# LucidVRSensorPCB_Side.net
KiCad netlist of a schematic drawn in EasyEDA
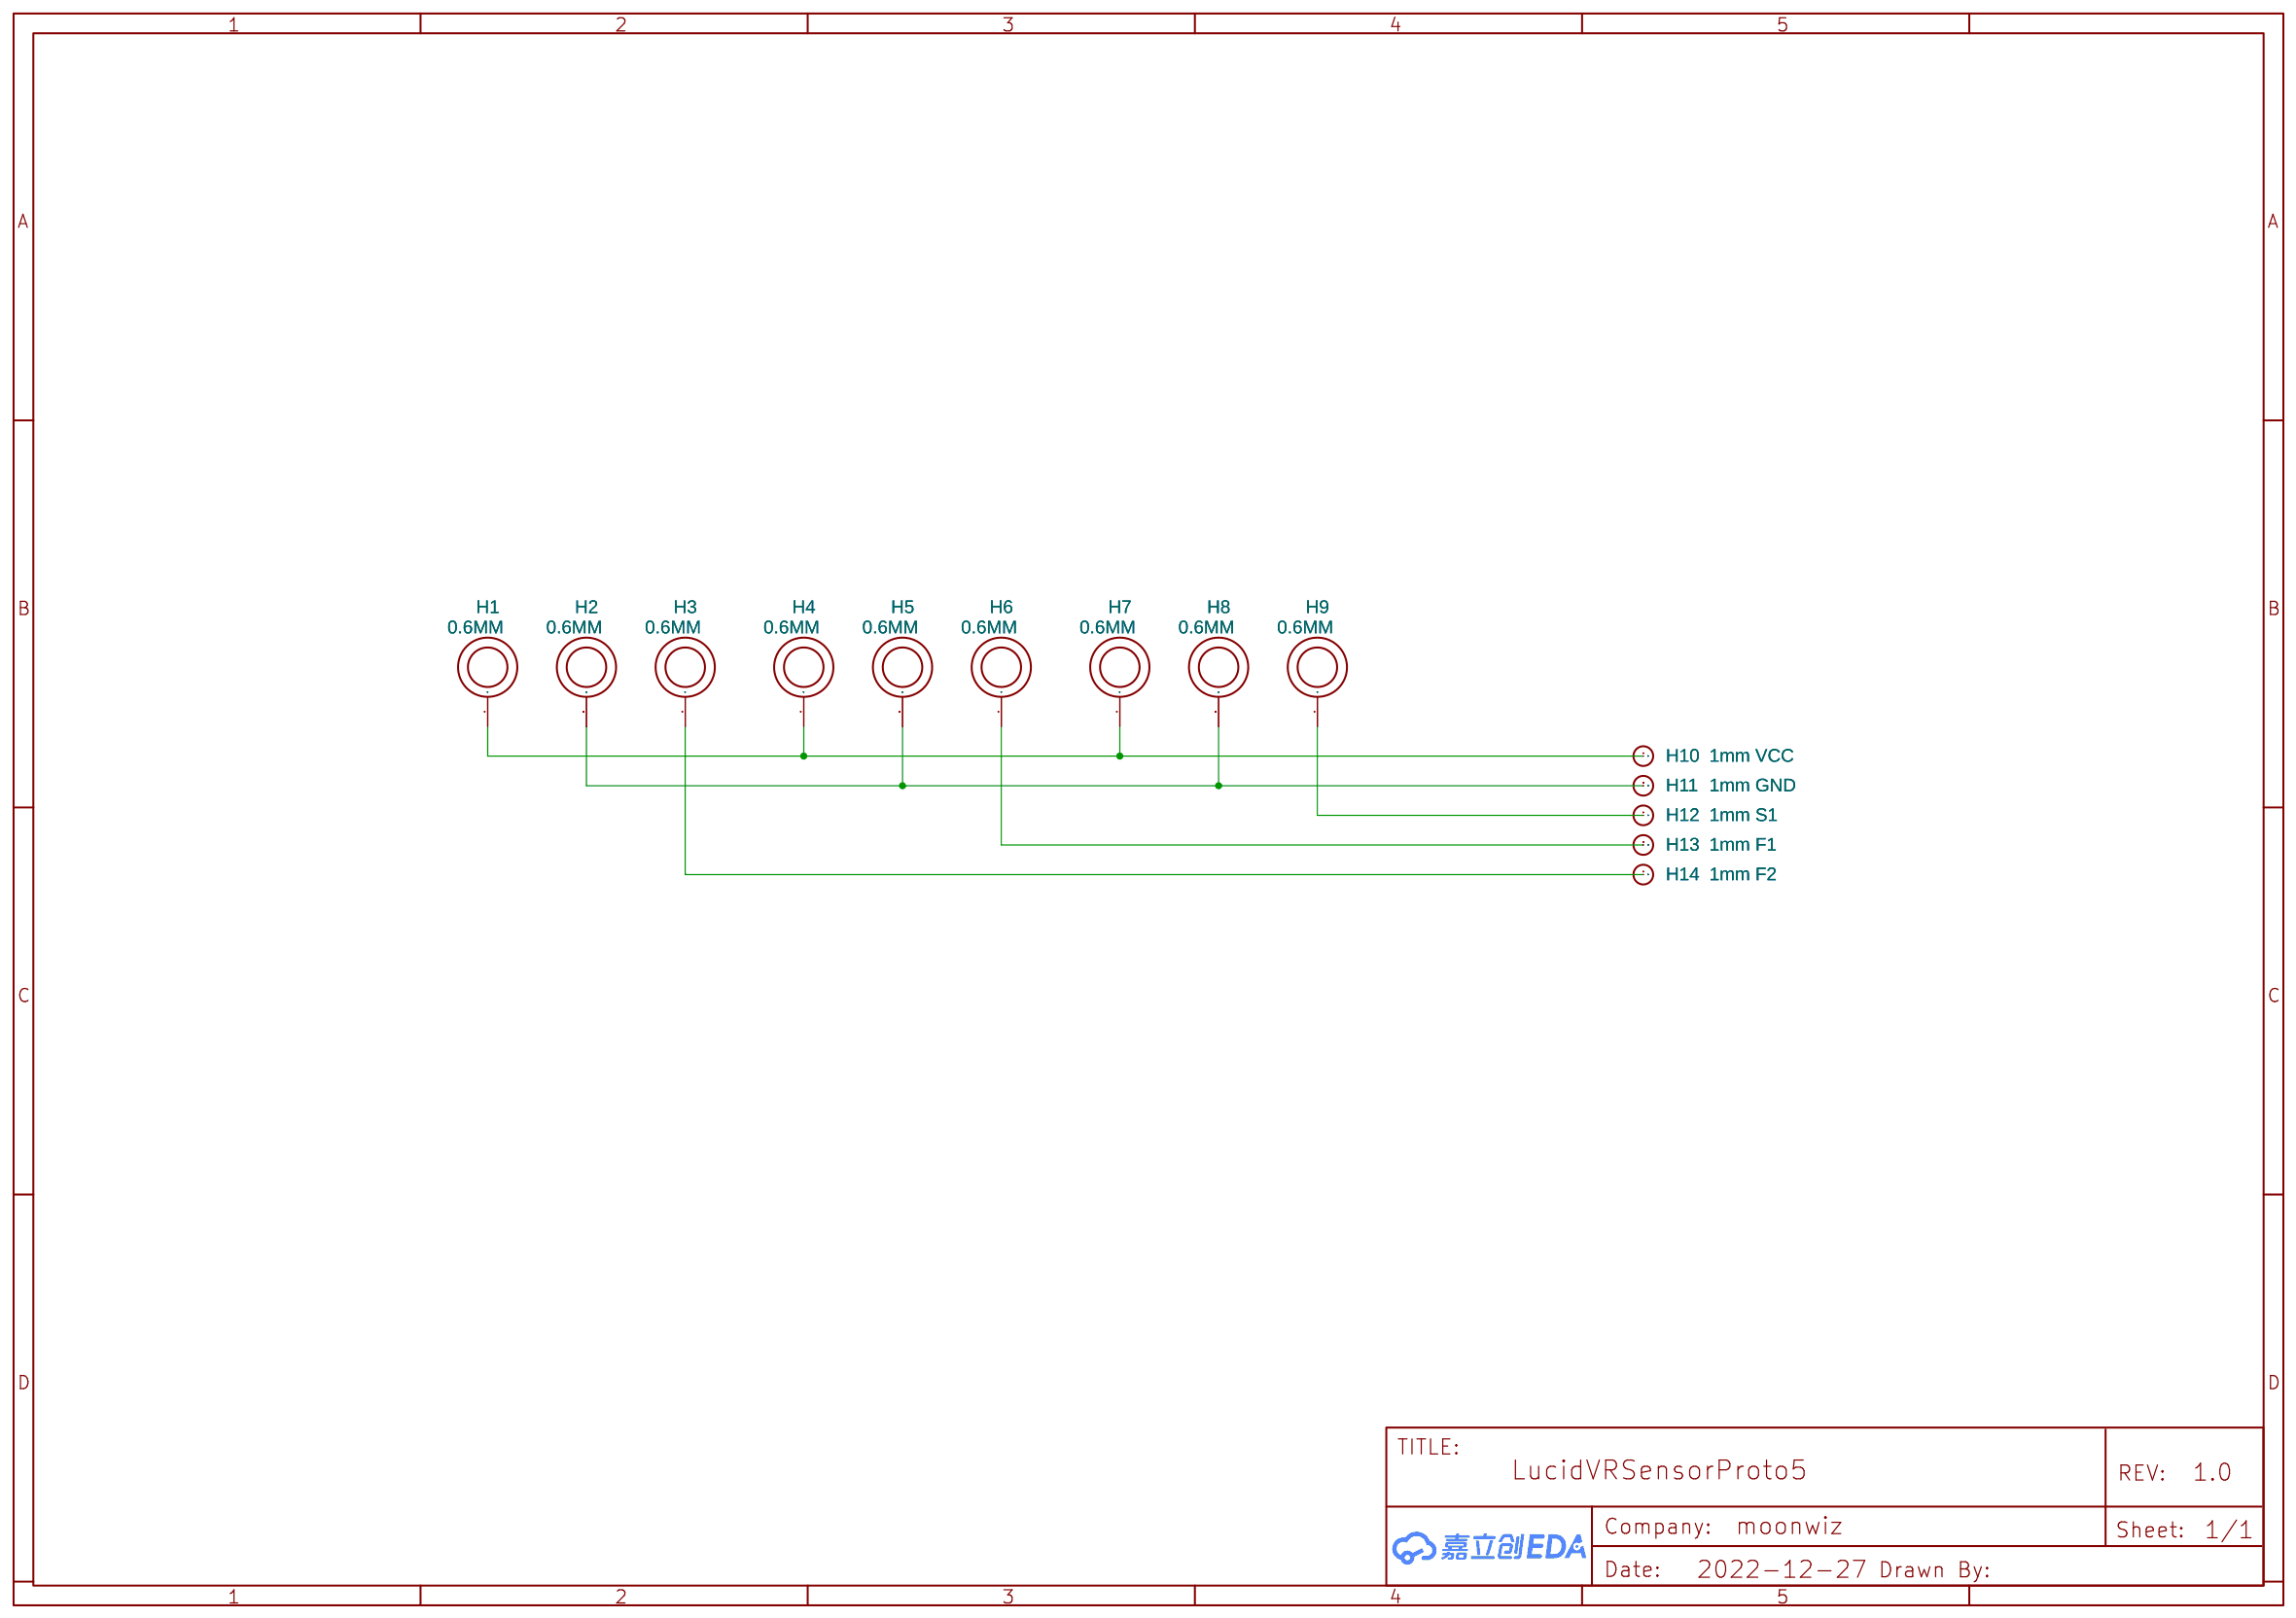
[diagram p0: schematic sheet]

(export (version "E")
  (design (tool "Eeschema 10.0.6"))
  (components
    (comp (ref "H1") (value "0.6MM") (libsource (lib "") (part "HOLE 3.4")))
    (comp (ref "H2") (value "0.6MM") (libsource (lib "") (part "HOLE 3.4")))
    (comp (ref "H3") (value "0.6MM") (libsource (lib "") (part "HOLE 3.4")))
    (comp (ref "H4") (value "0.6MM") (libsource (lib "") (part "HOLE 3.4")))
    (comp (ref "H5") (value "0.6MM") (libsource (lib "") (part "HOLE 3.4")))
    (comp (ref "H6") (value "0.6MM") (libsource (lib "") (part "HOLE 3.4")))
    (comp (ref "H7") (value "0.6MM") (libsource (lib "") (part "HOLE 3.4")))
    (comp (ref "H8") (value "0.6MM") (libsource (lib "") (part "HOLE 3.4")))
    (comp (ref "H9") (value "0.6MM") (libsource (lib "") (part "HOLE 3.4")))
    (comp (ref "H10")
      (value "1mm VCC")
      (fields (field (name "BOM_Supplier Part") "undefined"))
      (libsource (lib "") (part "Through_Hole_1mm"))
    )
    (comp (ref "H11")
      (value "1mm GND")
      (fields (field (name "BOM_Supplier Part") "undefined"))
      (libsource (lib "") (part "Through_Hole_1mm"))
    )
    (comp (ref "H12")
      (value "1mm S1")
      (fields (field (name "BOM_Supplier Part") "undefined"))
      (libsource (lib "") (part "Through_Hole_1mm"))
    )
    (comp (ref "H13")
      (value "1mm F1")
      (fields (field (name "BOM_Supplier Part") "undefined"))
      (libsource (lib "") (part "Through_Hole_1mm"))
    )
    (comp (ref "H14")
      (value "1mm F2")
      (fields (field (name "BOM_Supplier Part") "undefined"))
      (libsource (lib "") (part "Through_Hole_1mm"))
    )
  )
  (nets
    (net (code "1") (name "Net-(H1-Pad1)") (class "Default")
      (node (ref "H1") (pin "1") (pinfunction "1_1") (pintype "bidirectional"))
      (node (ref "H10") (pin "1") (pinfunction "1_1") (pintype "unspecified"))
      (node (ref "H4") (pin "1") (pinfunction "1_1") (pintype "bidirectional"))
      (node (ref "H7") (pin "1") (pinfunction "1_1") (pintype "bidirectional"))
    )
    (net (code "2") (name "Net-(H11-Pad1)") (class "Default")
      (node (ref "H11") (pin "1") (pinfunction "1_1") (pintype "unspecified"))
      (node (ref "H2") (pin "1") (pinfunction "1_1") (pintype "bidirectional"))
      (node (ref "H5") (pin "1") (pinfunction "1_1") (pintype "bidirectional"))
      (node (ref "H8") (pin "1") (pinfunction "1_1") (pintype "bidirectional"))
    )
    (net (code "3") (name "Net-(H12-Pad1)") (class "Default")
      (node (ref "H12") (pin "1") (pinfunction "1_1") (pintype "unspecified"))
      (node (ref "H9") (pin "1") (pinfunction "1_1") (pintype "bidirectional"))
    )
    (net (code "4") (name "Net-(H13-Pad1)") (class "Default")
      (node (ref "H13") (pin "1") (pinfunction "1_1") (pintype "unspecified"))
      (node (ref "H6") (pin "1") (pinfunction "1_1") (pintype "bidirectional"))
    )
    (net (code "5") (name "Net-(H14-Pad1)") (class "Default")
      (node (ref "H14") (pin "1") (pinfunction "1_1") (pintype "unspecified"))
      (node (ref "H3") (pin "1") (pinfunction "1_1") (pintype "bidirectional"))
    )
  )
)
